# powerRegulator.net
KiCad netlist of a schematic drawn in Altium Designer
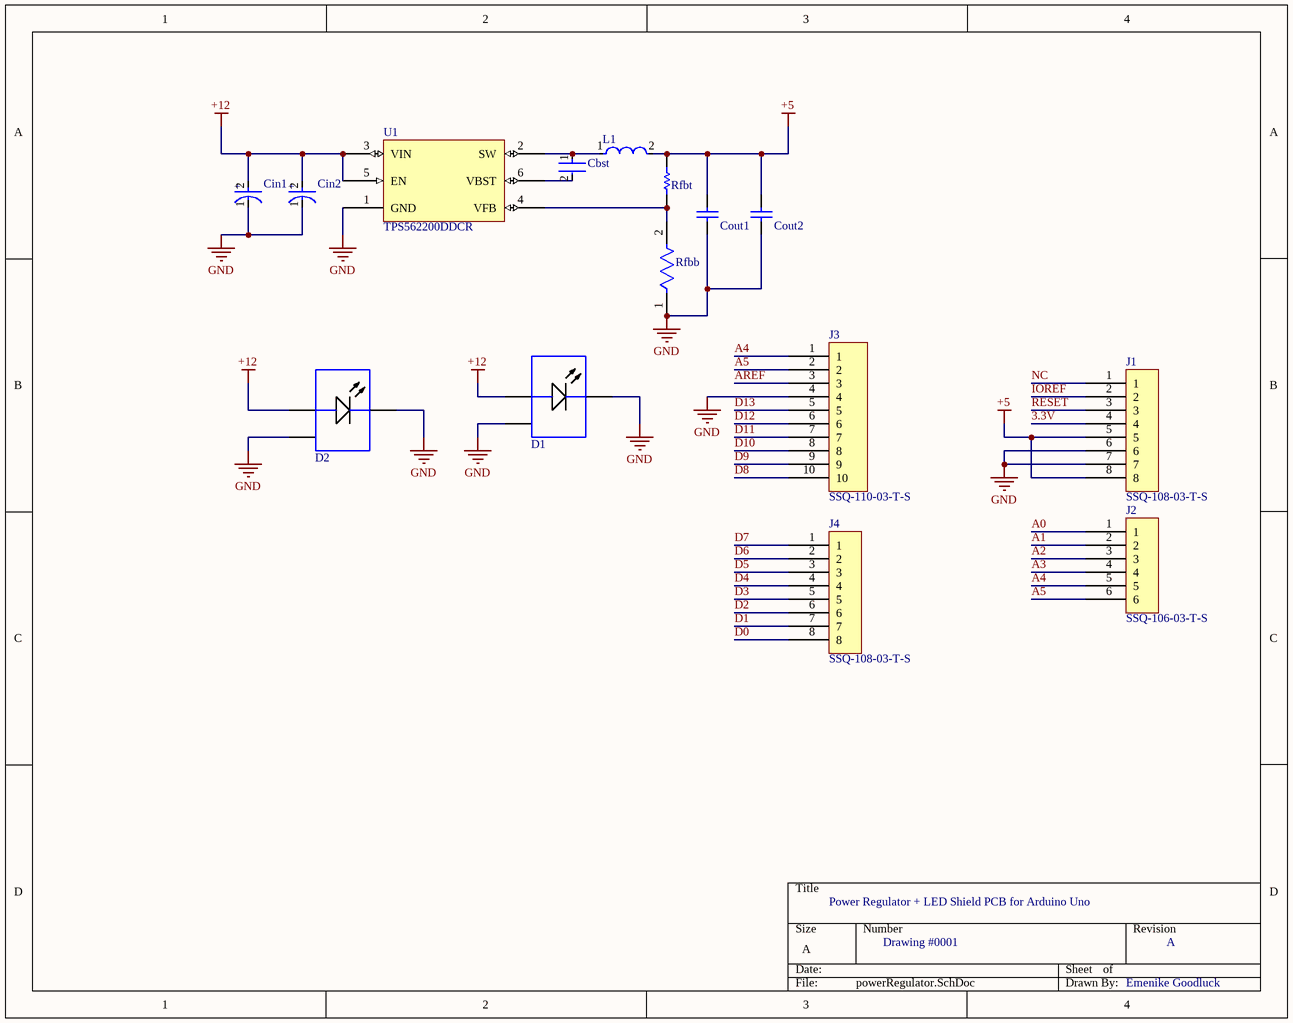
[diagram p0: powerRegulator.SchDoc]

(export (version "E")
  (design (tool "Eeschema 10.0.6"))
  (components
    (comp (ref "Cbst")
      (value "CC0805KRX7R8BB104")
      (footprint "FP-CC0805-0_85-MFG")
      (description "CAP CER 0.1UF 25V X7R 0805")
      (fields (field (name "TOLERANCE") "0.1") (field (name "MANUFACTURER") "Yageo"))
      (libsource (lib "Altium Content Vault") (part "11868f565c42a9108669ba33697ecf6"))
    )
    (comp (ref "Cin1")
      (value "T491D106K035AT")
      (footprint "FP-T491D106K035AT-MFG")
      (description "CAP TANT 10UF 10% 35V 2917")
      (fields (field (name "VOLTAGE") "35V") (field (name "TOLERANCE") "20%"))
      (libsource (lib "Altium Content Vault") (part "a00bbbee19879c290e62620ae7e47b1"))
    )
    (comp (ref "Cin2")
      (value "T491D106K035AT")
      (footprint "FP-T491D106K035AT-MFG")
      (description "CAP TANT 10UF 10% 35V 2917")
      (fields (field (name "VOLTAGE") "35V") (field (name "TOLERANCE") "20%"))
      (libsource (lib "Altium Content Vault") (part "a00bbbee19879c290e62620ae7e47b1"))
    )
    (comp (ref "Cout1")
      (value "C1608X5R1A226M080AC")
      (footprint "CAPC1608X100X20ML10")
      (description "Chip Capacitor, 22 uF, +/- 20%, 10 V, -55 to 85 degC, 0603 (1608 Metric), RoHS, Tape and Reel")
      (fields (field (name "MANUFACTURER") "TDK") (field (name "TOLERANCE") "±20%"))
      (libsource (lib "Altium Content Vault") (part "CAP-NP-2"))
    )
    (comp (ref "Cout2")
      (value "C1608X5R1A226M080AC")
      (footprint "CAPC1608X100X20ML10")
      (description "Chip Capacitor, 22 uF, +/- 20%, 10 V, -55 to 85 degC, 0603 (1608 Metric), RoHS, Tape and Reel")
      (fields (field (name "MANUFACTURER") "TDK") (field (name "TOLERANCE") "±20%"))
      (libsource (lib "Altium Content Vault") (part "CAP-NP-2"))
    )
    (comp (ref "D1")
      (value "MKRAWT-00-0000-0D0HG235H")
      (footprint "CREE-MK-R-2_V")
      (description "LED, White, 12 V, 2-Pin SMD, RoHS, Tape and Reel")
      (libsource (lib "Altium Content Vault") (part "LED_WHITE-3"))
    )
    (comp (ref "D2")
      (value "MKRAWT-00-0000-0D0HG235H")
      (footprint "CREE-MK-R-2_V")
      (description "LED, White, 12 V, 2-Pin SMD, RoHS, Tape and Reel")
      (libsource (lib "Altium Content Vault") (part "LED_WHITE-3"))
    )
    (comp (ref "J1")
      (value "SSQ-108-03-T-S")
      (footprint "SSQ-108-03-T-S-Footprint-1")
      (description "Headers & Wire Housings Tiger Buy Socket Strip with Square Tails, 0.100 Pitch")
      (libsource (lib "Carnegie Mellon University") (part "SSQ-108-03-T-S-Symbol-1"))
    )
    (comp (ref "J2")
      (value "SSQ-106-03-T-S")
      (footprint "SSQ-108-03-T-S-Footprint-1")
      (description "Headers & Wire Housings Tiger Buy Socket Strip with Square Tails, 0.100 Pitch")
      (libsource (lib "Carnegie Mellon University") (part "SSQ-106-03-T-S-Symbol-1"))
    )
    (comp (ref "J3")
      (value "SSQ-110-03-T-S")
      (footprint "SSQ-108-03-T-S-Footprint-1")
      (description "Headers & Wire Housings Tiger Buy Socket Strip with Square Tails, 0.100 Pitch")
      (libsource (lib "Carnegie Mellon University") (part "SSQ-110-03-T-S-Symbol-1"))
    )
    (comp (ref "J4")
      (value "SSQ-108-03-T-S")
      (footprint "SSQ-108-03-T-S-Footprint-1")
      (description "Headers & Wire Housings Tiger Buy Socket Strip with Square Tails, 0.100 Pitch")
      (libsource (lib "Carnegie Mellon University") (part "SSQ-108-03-T-S-Symbol-1"))
    )
    (comp (ref "L1")
      (value "NR6028T4R7M")
      (footprint "FP-NR6028-MFG")
      (description "SMD Power Inductors 4.7uH ±20% 2.7A 40.3mΩ")
      (fields (field (name "TOLERANCE") "20%"))
      (libsource (lib "Altium Content Vault") (part "725321dda6339637d4d059423bc1c3c"))
    )
    (comp (ref "Rfbb")
      (value "ERJ-1GNF1002C")
      (footprint "FP-ERJ1G-MFG")
      (description "10 kOhms ±1% 0.05W, 1/20W Chip Resistor 0201 (0603 Metric) Automotive AEC-Q200 Thick Film")
      (fields (field (name "OCTOPART") "https://octopart.com/erj-1gnf1002c-panasonic-55419697"))
      (libsource (lib "Altium Content Vault") (part "1029c3af85768c4190bb7ad29bc67b5"))
    )
    (comp (ref "Rfbt")
      (value "CRCW020156K2FNED")
      (footprint "RESC0603X28X15NL05T05")
      (fields (field (name "MANUFACTURER") "Vishay Dale"))
      (libsource (lib "Altium Content Vault") (part "RES"))
    )
    (comp (ref "U1")
      (value "TPS562200DDCR")
      (footprint "SOIC127P280X110-6N")
      (description "Buck Switching Regulator IC Positive Adjustable 0.765V 1 Output 2A SOT-23-6 Thin, TSOT-23-6")
      (libsource (lib "Carnegie Mellon University") (part "TPS562200DDCR-Symbol-1"))
    )
  )
  (nets
    (net (code "1") (name "+5") (class "Default")
      (node (ref "Cout1") (pin "2") (pinfunction "2_2") (pintype "passive"))
      (node (ref "Cout2") (pin "2") (pinfunction "2_2") (pintype "passive"))
      (node (ref "J1") (pin "5") (pinfunction "5_5") (pintype "passive"))
      (node (ref "J1") (pin "8") (pinfunction "8_8") (pintype "passive"))
      (node (ref "L1") (pin "2") (pinfunction "2_2") (pintype "passive"))
      (node (ref "Rfbt") (pin "2") (pinfunction "2_2") (pintype "passive"))
    )
    (net (code "2") (name "+12") (class "Default")
      (node (ref "Cin1") (pin "2") (pinfunction "A_2") (pintype "passive"))
      (node (ref "Cin2") (pin "2") (pinfunction "A_2") (pintype "passive"))
      (node (ref "D1") (pin "1") (pinfunction "A_1") (pintype "passive"))
      (node (ref "D2") (pin "1") (pinfunction "A_1") (pintype "passive"))
      (node (ref "U1") (pin "3") (pinfunction "VIN_3") (pintype "bidirectional"))
      (node (ref "U1") (pin "5") (pinfunction "EN_5") (pintype "input"))
    )
    (net (code "3") (name "/3.3V") (class "Default")
      (node (ref "J1") (pin "4") (pinfunction "4_4") (pintype "passive"))
    )
    (net (code "4") (name "/A0") (class "Default")
      (node (ref "J2") (pin "1") (pinfunction "1_1") (pintype "passive"))
    )
    (net (code "5") (name "/A1") (class "Default")
      (node (ref "J2") (pin "2") (pinfunction "2_2") (pintype "passive"))
    )
    (net (code "6") (name "/A2") (class "Default")
      (node (ref "J2") (pin "3") (pinfunction "3_3") (pintype "passive"))
    )
    (net (code "7") (name "/A3") (class "Default")
      (node (ref "J2") (pin "4") (pinfunction "4_4") (pintype "passive"))
    )
    (net (code "8") (name "/A4") (class "Default")
      (node (ref "J2") (pin "5") (pinfunction "5_5") (pintype "passive"))
      (node (ref "J3") (pin "1") (pinfunction "1_1") (pintype "passive"))
    )
    (net (code "9") (name "/A5") (class "Default")
      (node (ref "J2") (pin "6") (pinfunction "6_6") (pintype "passive"))
      (node (ref "J3") (pin "2") (pinfunction "2_2") (pintype "passive"))
    )
    (net (code "10") (name "/AREF") (class "Default")
      (node (ref "J3") (pin "3") (pinfunction "3_3") (pintype "passive"))
    )
    (net (code "11") (name "/D0") (class "Default")
      (node (ref "J4") (pin "8") (pinfunction "8_8") (pintype "passive"))
    )
    (net (code "12") (name "/D1") (class "Default")
      (node (ref "J4") (pin "7") (pinfunction "7_7") (pintype "passive"))
    )
    (net (code "13") (name "/D2") (class "Default")
      (node (ref "J4") (pin "6") (pinfunction "6_6") (pintype "passive"))
    )
    (net (code "14") (name "/D3") (class "Default")
      (node (ref "J4") (pin "5") (pinfunction "5_5") (pintype "passive"))
    )
    (net (code "15") (name "/D4") (class "Default")
      (node (ref "J4") (pin "4") (pinfunction "4_4") (pintype "passive"))
    )
    (net (code "16") (name "/D5") (class "Default")
      (node (ref "J4") (pin "3") (pinfunction "3_3") (pintype "passive"))
    )
    (net (code "17") (name "/D6") (class "Default")
      (node (ref "J4") (pin "2") (pinfunction "2_2") (pintype "passive"))
    )
    (net (code "18") (name "/D7") (class "Default")
      (node (ref "J4") (pin "1") (pinfunction "1_1") (pintype "passive"))
    )
    (net (code "19") (name "/D8") (class "Default")
      (node (ref "J3") (pin "10") (pinfunction "10_10") (pintype "passive"))
    )
    (net (code "20") (name "/D9") (class "Default")
      (node (ref "J3") (pin "9") (pinfunction "9_9") (pintype "passive"))
    )
    (net (code "21") (name "/D10") (class "Default")
      (node (ref "J3") (pin "8") (pinfunction "8_8") (pintype "passive"))
    )
    (net (code "22") (name "/D11") (class "Default")
      (node (ref "J3") (pin "7") (pinfunction "7_7") (pintype "passive"))
    )
    (net (code "23") (name "/D12") (class "Default")
      (node (ref "J3") (pin "6") (pinfunction "6_6") (pintype "passive"))
    )
    (net (code "24") (name "/D13") (class "Default")
      (node (ref "J3") (pin "5") (pinfunction "5_5") (pintype "passive"))
    )
    (net (code "25") (name "/IOREF") (class "Default")
      (node (ref "J1") (pin "2") (pinfunction "2_2") (pintype "passive"))
    )
    (net (code "26") (name "/NC") (class "Default")
      (node (ref "J1") (pin "1") (pinfunction "1_1") (pintype "passive"))
    )
    (net (code "27") (name "/RESET") (class "Default")
      (node (ref "J1") (pin "3") (pinfunction "3_3") (pintype "passive"))
    )
    (net (code "28") (name "GND") (class "Default")
      (node (ref "Cin1") (pin "1") (pinfunction "C_1") (pintype "passive"))
      (node (ref "Cin2") (pin "1") (pinfunction "C_1") (pintype "passive"))
      (node (ref "Cout1") (pin "1") (pinfunction "1_1") (pintype "passive"))
      (node (ref "Cout2") (pin "1") (pinfunction "1_1") (pintype "passive"))
      (node (ref "D1") (pin "2") (pinfunction "K_2") (pintype "passive"))
      (node (ref "D1") (pin "3") (pinfunction "EP_3") (pintype "passive"))
      (node (ref "D2") (pin "2") (pinfunction "K_2") (pintype "passive"))
      (node (ref "D2") (pin "3") (pinfunction "EP_3") (pintype "passive"))
      (node (ref "J1") (pin "6") (pinfunction "6_6") (pintype "passive"))
      (node (ref "J1") (pin "7") (pinfunction "7_7") (pintype "passive"))
      (node (ref "J3") (pin "4") (pinfunction "4_4") (pintype "passive"))
      (node (ref "Rfbb") (pin "1") (pinfunction "1_1") (pintype "passive"))
      (node (ref "U1") (pin "1") (pinfunction "GND_1") (pintype "power_in"))
    )
    (net (code "29") (name "Net-(U1-SW)") (class "Default")
      (node (ref "Cbst") (pin "1") (pinfunction "1_1") (pintype "passive"))
      (node (ref "L1") (pin "1") (pinfunction "1_1") (pintype "passive"))
      (node (ref "U1") (pin "2") (pinfunction "SW_2") (pintype "bidirectional"))
    )
    (net (code "30") (name "Net-(U1-VBST)") (class "Default")
      (node (ref "Cbst") (pin "2") (pinfunction "2_2") (pintype "passive"))
      (node (ref "U1") (pin "6") (pinfunction "VBST_6") (pintype "bidirectional"))
    )
    (net (code "31") (name "Net-(U1-VFB)") (class "Default")
      (node (ref "Rfbb") (pin "2") (pinfunction "2_2") (pintype "passive"))
      (node (ref "Rfbt") (pin "1") (pinfunction "1_1") (pintype "passive"))
      (node (ref "U1") (pin "4") (pinfunction "VFB_4") (pintype "bidirectional"))
    )
  )
)
